# PortExpanderCircuit.net
KiCad netlist of a schematic drawn in EAGLE
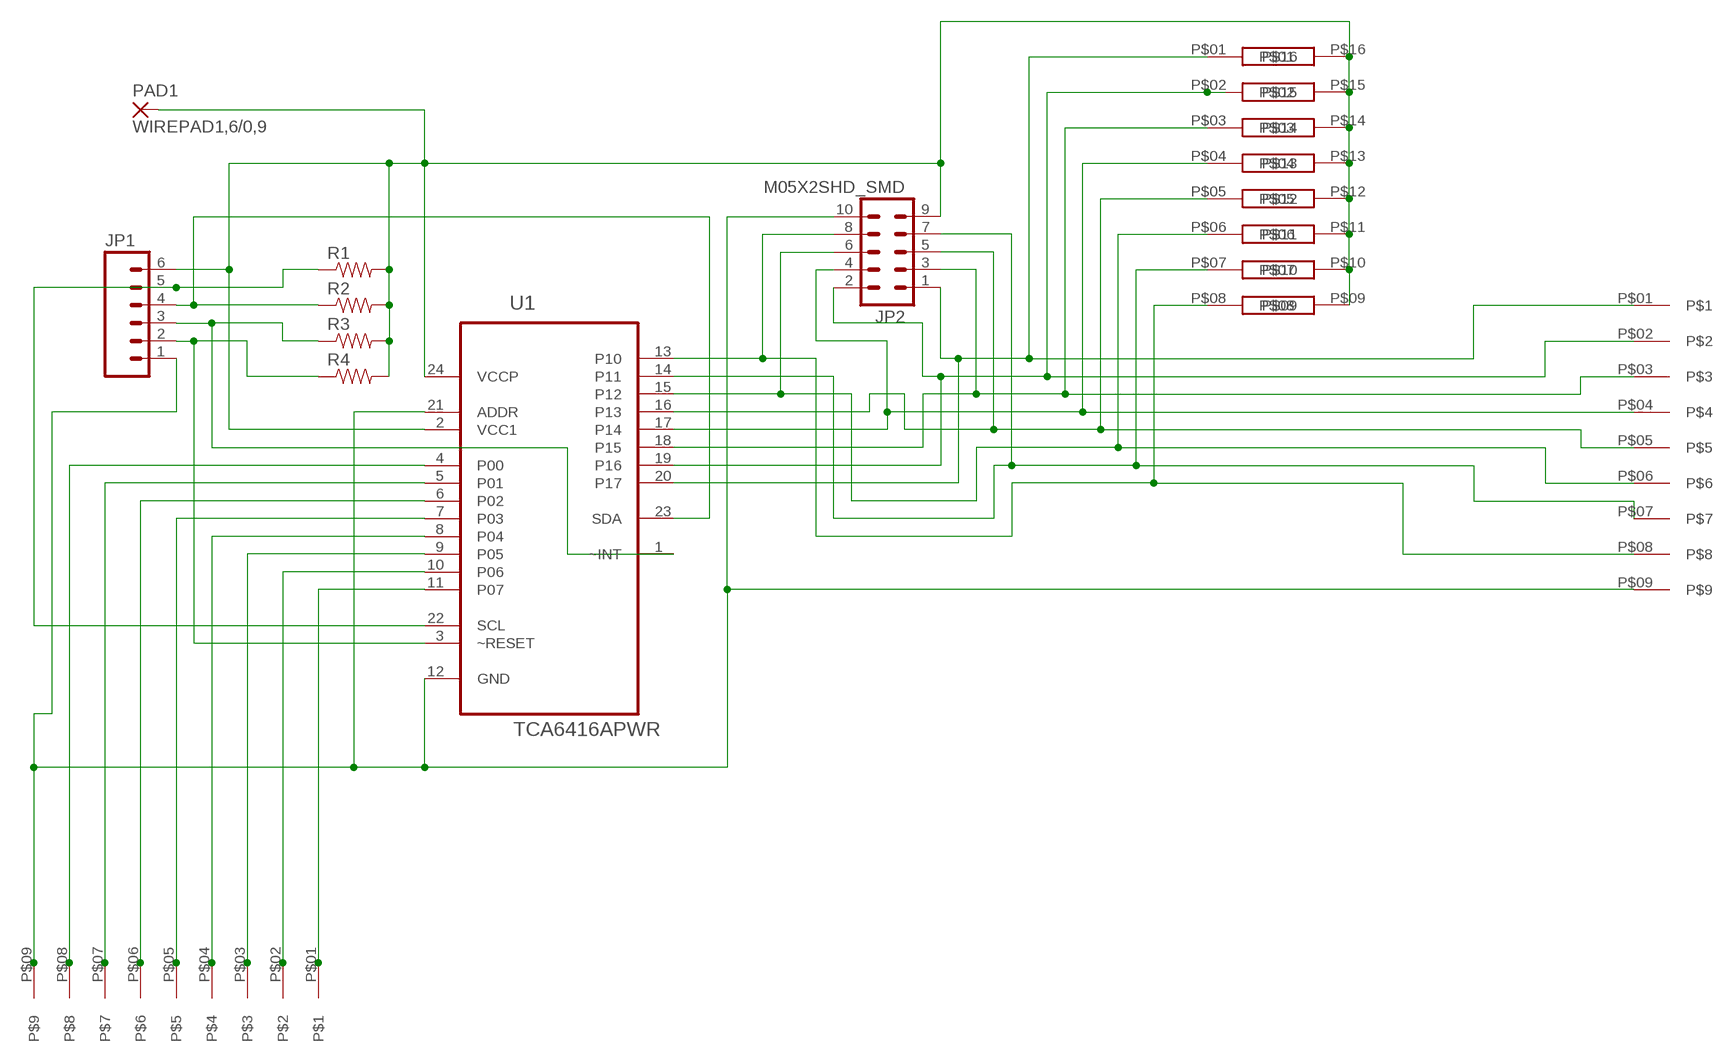
[diagram p0: schematic, sheet 1]

(export (version "E")
  (design (tool "Eeschema 10.0.6"))
  (components
    (comp (ref "JP1")
      (value "M06LOCK_LONGPADS")
      (footprint "eagle-import:1X06_LOCK_LONGPADS")
      (libsource (lib "eagle-import") (part "M06LOCK_LONGPADS"))
    )
    (comp (ref "JP2")
      (value "M05X2SHD_SMD")
      (footprint "eagle-import:2X5-SHROUDED_SMD")
      (libsource (lib "eagle-import") (part "M05X2SHD_SMD"))
    )
    (comp (ref "PAD1")
      (value "WIREPAD1,6/0,9")
      (footprint "eagle-import:1,6_0,9")
      (libsource (lib "eagle-import") (part "WIREPAD1,6/0,9"))
    )
    (comp (ref "R1")
      (value "RESISTOR0805-RES")
      (footprint "eagle-import:0805")
      (libsource (lib "eagle-import") (part "RESISTOR0805-RES"))
    )
    (comp (ref "R2")
      (value "RESISTOR0805-RES")
      (footprint "eagle-import:0805")
      (libsource (lib "eagle-import") (part "RESISTOR0805-RES"))
    )
    (comp (ref "R3")
      (value "RESISTOR0805-RES")
      (footprint "eagle-import:0805")
      (libsource (lib "eagle-import") (part "RESISTOR0805-RES"))
    )
    (comp (ref "R4")
      (value "RESISTOR0805-RES")
      (footprint "eagle-import:0805")
      (libsource (lib "eagle-import") (part "RESISTOR0805-RES"))
    )
    (comp (ref "U$1")
      (value "TECONN_FPC_FFC_84953-9")
      (footprint "eagle-import:TECONN_84953-9")
      (libsource (lib "eagle-import") (part "TECONN_FPC_FFC_84953-9"))
    )
    (comp (ref "U$2")
      (value "TECONN_FPC_FFC_84953-9")
      (footprint "eagle-import:TECONN_84953-9")
      (libsource (lib "eagle-import") (part "TECONN_FPC_FFC_84953-9"))
    )
    (comp (ref "U$3")
      (value "EXB-A10P_8_RESISTOR_ARRAY")
      (footprint "eagle-import:EXB-A10P")
      (libsource (lib "eagle-import") (part "EXB-A10P_8_RESISTOR_ARRAY"))
    )
    (comp (ref "U1")
      (value "TCA6416APWR")
      (footprint "eagle-import:SOP65P640X120-24N")
      (libsource (lib "eagle-import") (part "TCA6416APWR"))
    )
  )
  (nets
    (net (code "1") (name "Net-(PAD1-P)") (class "Default")
      (node (ref "JP1") (pin "6") (pinfunction "6_6") (pintype "passive"))
      (node (ref "JP2") (pin "9") (pinfunction "9_9") (pintype "passive"))
      (node (ref "PAD1") (pin "1") (pinfunction "P_1") (pintype "passive"))
      (node (ref "R1") (pin "2") (pinfunction "2_2") (pintype "passive"))
      (node (ref "R2") (pin "2") (pinfunction "2_2") (pintype "passive"))
      (node (ref "R3") (pin "2") (pinfunction "2_2") (pintype "passive"))
      (node (ref "R4") (pin "2") (pinfunction "2_2") (pintype "passive"))
      (node (ref "U$3") (pin "P$09") (pinfunction "P$09_P$09") (pintype "bidirectional"))
      (node (ref "U$3") (pin "P$10") (pinfunction "P$10_P$10") (pintype "bidirectional"))
      (node (ref "U$3") (pin "P$11") (pinfunction "P$11_P$11") (pintype "bidirectional"))
      (node (ref "U$3") (pin "P$12") (pinfunction "P$12_P$12") (pintype "bidirectional"))
      (node (ref "U$3") (pin "P$13") (pinfunction "P$13_P$13") (pintype "bidirectional"))
      (node (ref "U$3") (pin "P$14") (pinfunction "P$14_P$14") (pintype "bidirectional"))
      (node (ref "U$3") (pin "P$15") (pinfunction "P$15_P$15") (pintype "bidirectional"))
      (node (ref "U$3") (pin "P$16") (pinfunction "P$16_P$16") (pintype "bidirectional"))
      (node (ref "U1") (pin "2") (pinfunction "VCC1_2") (pintype "power_in"))
      (node (ref "U1") (pin "24") (pinfunction "VCCP_24") (pintype "power_in"))
    )
    (net (code "2") (name "Net-(U$1-P$1)") (class "Default")
      (node (ref "JP2") (pin "1") (pinfunction "1_1") (pintype "passive"))
      (node (ref "U$1") (pin "P$01") (pinfunction "P$1_P$01") (pintype "bidirectional"))
      (node (ref "U$3") (pin "P$01") (pinfunction "P$01_P$01") (pintype "bidirectional"))
      (node (ref "U1") (pin "20") (pinfunction "P17_20") (pintype "bidirectional"))
    )
    (net (code "3") (name "Net-(U$1-P$2)") (class "Default")
      (node (ref "JP2") (pin "2") (pinfunction "2_2") (pintype "passive"))
      (node (ref "U$1") (pin "P$02") (pinfunction "P$2_P$02") (pintype "bidirectional"))
      (node (ref "U$3") (pin "P$02") (pinfunction "P$02_P$02") (pintype "bidirectional"))
      (node (ref "U1") (pin "19") (pinfunction "P16_19") (pintype "bidirectional"))
    )
    (net (code "4") (name "Net-(U$1-P$3)") (class "Default")
      (node (ref "JP2") (pin "3") (pinfunction "3_3") (pintype "passive"))
      (node (ref "U$1") (pin "P$03") (pinfunction "P$3_P$03") (pintype "bidirectional"))
      (node (ref "U$3") (pin "P$03") (pinfunction "P$03_P$03") (pintype "bidirectional"))
      (node (ref "U1") (pin "18") (pinfunction "P15_18") (pintype "bidirectional"))
    )
    (net (code "5") (name "Net-(U$1-P$4)") (class "Default")
      (node (ref "JP2") (pin "4") (pinfunction "4_4") (pintype "passive"))
      (node (ref "U$1") (pin "P$04") (pinfunction "P$4_P$04") (pintype "bidirectional"))
      (node (ref "U$3") (pin "P$04") (pinfunction "P$04_P$04") (pintype "bidirectional"))
      (node (ref "U1") (pin "17") (pinfunction "P14_17") (pintype "bidirectional"))
    )
    (net (code "6") (name "Net-(U$1-P$5)") (class "Default")
      (node (ref "JP2") (pin "5") (pinfunction "5_5") (pintype "passive"))
      (node (ref "U$1") (pin "P$05") (pinfunction "P$5_P$05") (pintype "bidirectional"))
      (node (ref "U$3") (pin "P$05") (pinfunction "P$05_P$05") (pintype "bidirectional"))
      (node (ref "U1") (pin "16") (pinfunction "P13_16") (pintype "bidirectional"))
    )
    (net (code "7") (name "Net-(U$1-P$6)") (class "Default")
      (node (ref "JP2") (pin "6") (pinfunction "6_6") (pintype "passive"))
      (node (ref "U$1") (pin "P$06") (pinfunction "P$6_P$06") (pintype "bidirectional"))
      (node (ref "U$3") (pin "P$06") (pinfunction "P$06_P$06") (pintype "bidirectional"))
      (node (ref "U1") (pin "15") (pinfunction "P12_15") (pintype "bidirectional"))
    )
    (net (code "8") (name "Net-(U$1-P$7)") (class "Default")
      (node (ref "JP2") (pin "7") (pinfunction "7_7") (pintype "passive"))
      (node (ref "U$1") (pin "P$07") (pinfunction "P$7_P$07") (pintype "bidirectional"))
      (node (ref "U$3") (pin "P$07") (pinfunction "P$07_P$07") (pintype "bidirectional"))
      (node (ref "U1") (pin "14") (pinfunction "P11_14") (pintype "bidirectional"))
    )
    (net (code "9") (name "Net-(U$1-P$8)") (class "Default")
      (node (ref "JP2") (pin "8") (pinfunction "8_8") (pintype "passive"))
      (node (ref "U$1") (pin "P$08") (pinfunction "P$8_P$08") (pintype "bidirectional"))
      (node (ref "U$3") (pin "P$08") (pinfunction "P$08_P$08") (pintype "bidirectional"))
      (node (ref "U1") (pin "13") (pinfunction "P10_13") (pintype "bidirectional"))
    )
    (net (code "10") (name "Net-(U$1-P$9)") (class "Default")
      (node (ref "JP1") (pin "1") (pinfunction "1_1") (pintype "passive"))
      (node (ref "JP2") (pin "10") (pinfunction "10_10") (pintype "passive"))
      (node (ref "U$1") (pin "P$09") (pinfunction "P$9_P$09") (pintype "bidirectional"))
      (node (ref "U$2") (pin "P$09") (pinfunction "P$9_P$09") (pintype "bidirectional"))
      (node (ref "U1") (pin "12") (pinfunction "GND_12") (pintype "passive"))
      (node (ref "U1") (pin "21") (pinfunction "ADDR_21") (pintype "input"))
    )
    (net (code "11") (name "Net-(U$2-P$1)") (class "Default")
      (node (ref "U$2") (pin "P$01") (pinfunction "P$1_P$01") (pintype "bidirectional"))
      (node (ref "U1") (pin "11") (pinfunction "P07_11") (pintype "bidirectional"))
    )
    (net (code "12") (name "Net-(U$2-P$2)") (class "Default")
      (node (ref "U$2") (pin "P$02") (pinfunction "P$2_P$02") (pintype "bidirectional"))
      (node (ref "U1") (pin "10") (pinfunction "P06_10") (pintype "bidirectional"))
    )
    (net (code "13") (name "Net-(U$2-P$3)") (class "Default")
      (node (ref "U$2") (pin "P$03") (pinfunction "P$3_P$03") (pintype "bidirectional"))
      (node (ref "U1") (pin "9") (pinfunction "P05_9") (pintype "bidirectional"))
    )
    (net (code "14") (name "Net-(U$2-P$4)") (class "Default")
      (node (ref "U$2") (pin "P$04") (pinfunction "P$4_P$04") (pintype "bidirectional"))
      (node (ref "U1") (pin "8") (pinfunction "P04_8") (pintype "bidirectional"))
    )
    (net (code "15") (name "Net-(U$2-P$5)") (class "Default")
      (node (ref "U$2") (pin "P$05") (pinfunction "P$5_P$05") (pintype "bidirectional"))
      (node (ref "U1") (pin "7") (pinfunction "P03_7") (pintype "bidirectional"))
    )
    (net (code "16") (name "Net-(U$2-P$6)") (class "Default")
      (node (ref "U$2") (pin "P$06") (pinfunction "P$6_P$06") (pintype "bidirectional"))
      (node (ref "U1") (pin "6") (pinfunction "P02_6") (pintype "bidirectional"))
    )
    (net (code "17") (name "Net-(U$2-P$7)") (class "Default")
      (node (ref "U$2") (pin "P$07") (pinfunction "P$7_P$07") (pintype "bidirectional"))
      (node (ref "U1") (pin "5") (pinfunction "P01_5") (pintype "bidirectional"))
    )
    (net (code "18") (name "Net-(U$2-P$8)") (class "Default")
      (node (ref "U$2") (pin "P$08") (pinfunction "P$8_P$08") (pintype "bidirectional"))
      (node (ref "U1") (pin "4") (pinfunction "P00_4") (pintype "bidirectional"))
    )
    (net (code "19") (name "Net-(U1-SCL)") (class "Default")
      (node (ref "JP1") (pin "5") (pinfunction "5_5") (pintype "passive"))
      (node (ref "R1") (pin "1") (pinfunction "1_1") (pintype "passive"))
      (node (ref "U1") (pin "22") (pinfunction "SCL_22") (pintype "input"))
    )
    (net (code "20") (name "Net-(U1-SDA)") (class "Default")
      (node (ref "JP1") (pin "4") (pinfunction "4_4") (pintype "passive"))
      (node (ref "R2") (pin "1") (pinfunction "1_1") (pintype "passive"))
      (node (ref "U1") (pin "23") (pinfunction "SDA_23") (pintype "bidirectional"))
    )
    (net (code "21") (name "Net-(U1-~{INT})") (class "Default")
      (node (ref "JP1") (pin "3") (pinfunction "3_3") (pintype "passive"))
      (node (ref "R3") (pin "1") (pinfunction "1_1") (pintype "passive"))
      (node (ref "U1") (pin "1") (pinfunction "~{INT}_1") (pintype "output"))
    )
    (net (code "22") (name "Net-(U1-~{RESET})") (class "Default")
      (node (ref "JP1") (pin "2") (pinfunction "2_2") (pintype "passive"))
      (node (ref "R4") (pin "1") (pinfunction "1_1") (pintype "passive"))
      (node (ref "U1") (pin "3") (pinfunction "~{RESET}_3") (pintype "input"))
    )
  )
)
